# Auction_Single_RevB_Final.net
KiCad netlist of a schematic drawn in EAGLE
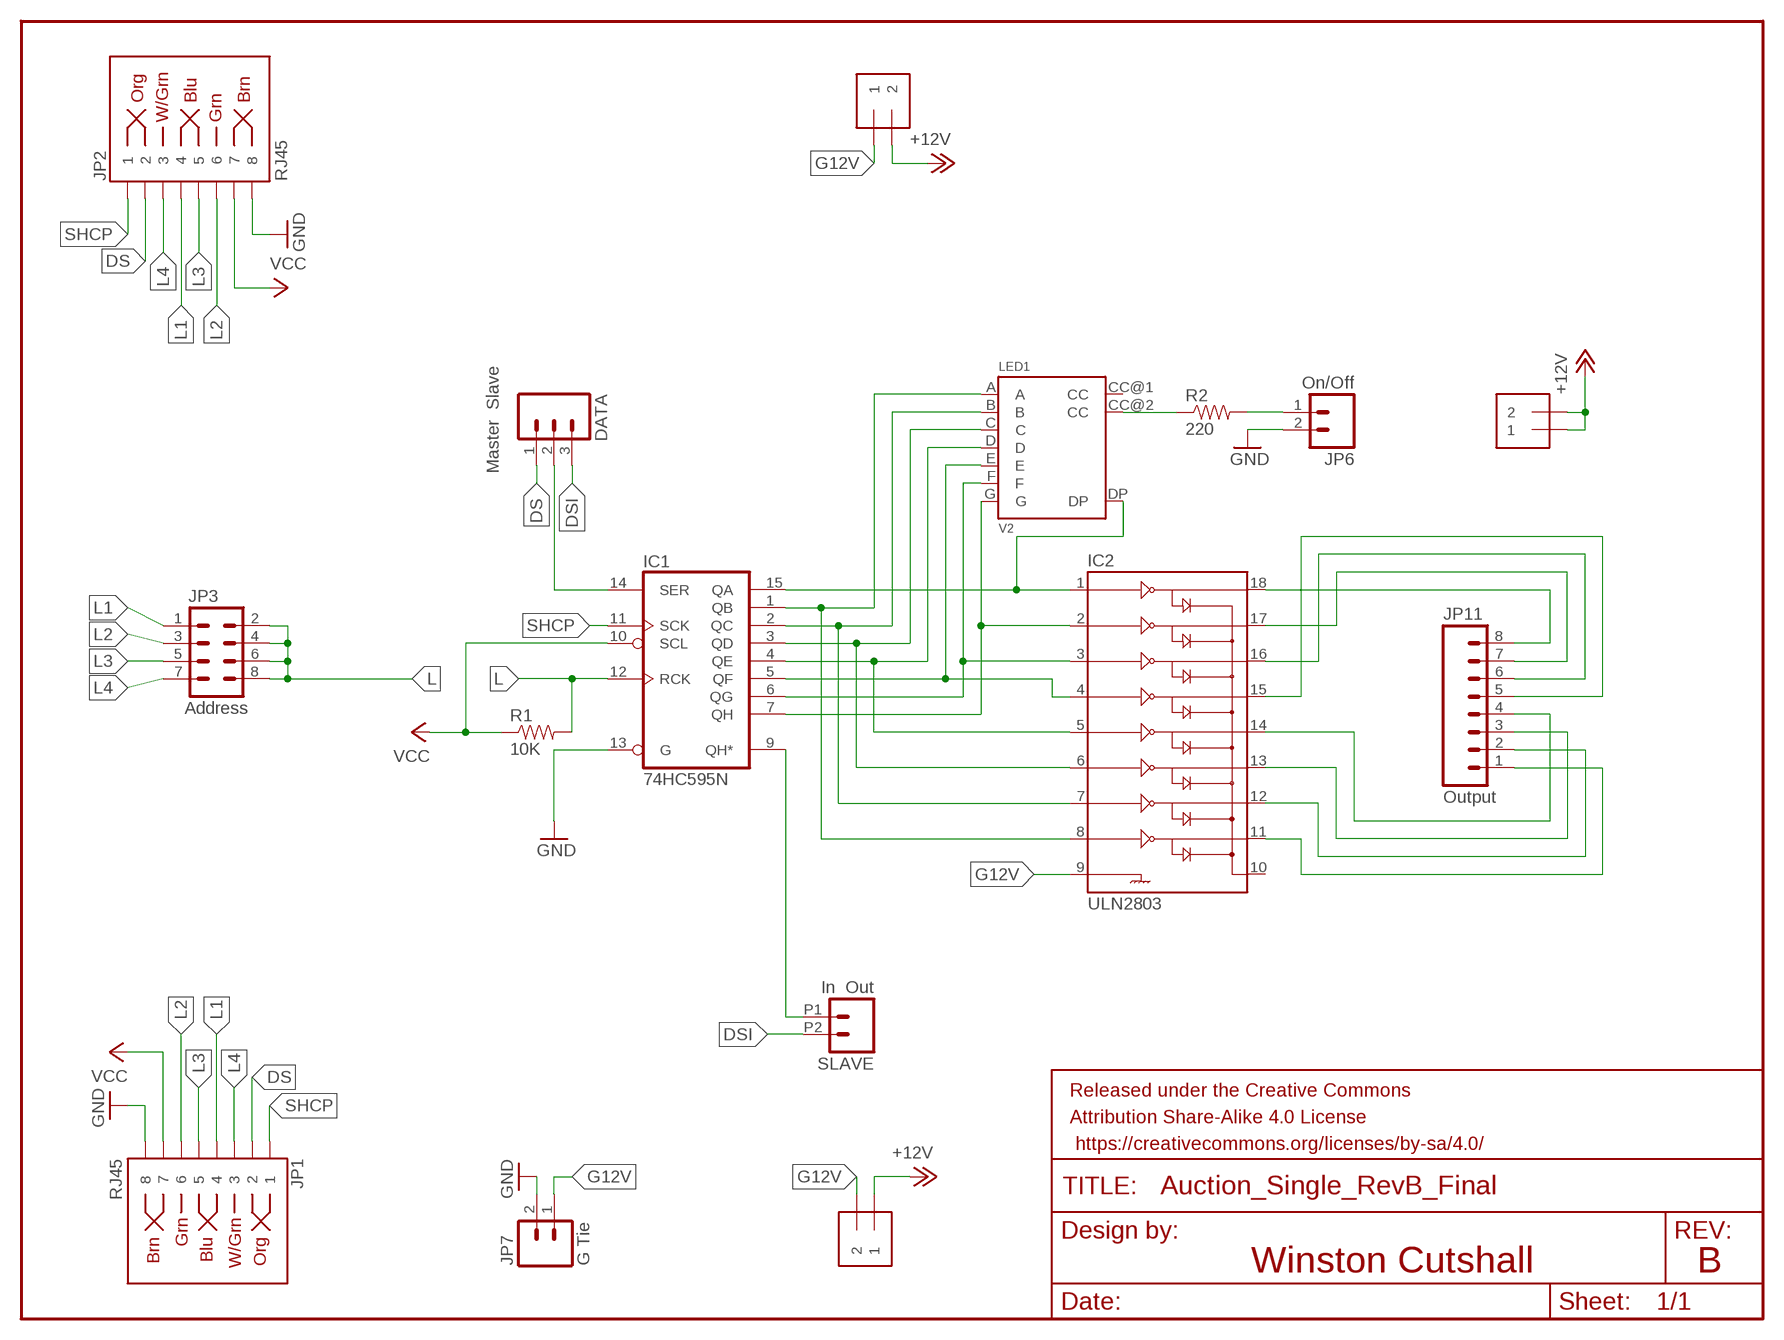
[diagram p0: schematic, sheet 1]

(export (version "E")
  (design (tool "Eeschema 10.0.6"))
  (components
    (comp (ref "DATA")
      (value "Master Slave")
      (footprint "eagle-import:1X03")
      (fields (field (name "MPN") "2211S-03G"))
      (libsource (lib "eagle-import") (part "M03PTH"))
    )
    (comp (ref "FRAME1")
      (value "FRAME-LETTER")
      (footprint "eagle-import:CREATIVE_COMMONS")
      (libsource (lib "eagle-import") (part "FRAME-LETTER"))
    )
    (comp (ref "IC1")
      (value "74HC595N")
      (footprint "eagle-import:DIL16")
      (fields (field (name "MF") "TEXAS INSTRUMENTS") (field (name "MPN") "SN74HC595N"))
      (libsource (lib "eagle-import") (part "74595NHC"))
    )
    (comp (ref "IC2")
      (value "ULN2803")
      (footprint "eagle-import:DIL18")
      (fields (field (name "MF") "Arrow Electronics") (field (name "MPN") "ULN2803A"))
      (libsource (lib "eagle-import") (part "ULN2803DIP"))
    )
    (comp (ref "JP1")
      (value "RJ45")
      (footprint "eagle-import:RJ45-8")
      (fields (field (name "MPN") "54602-908LF"))
      (libsource (lib "eagle-import") (part "RJ45-8PTH"))
    )
    (comp (ref "JP2")
      (value "RJ45")
      (footprint "eagle-import:RJ45-8")
      (fields (field (name "MPN") "54602-908LF"))
      (libsource (lib "eagle-import") (part "RJ45-8PTH"))
    )
    (comp (ref "JP3")
      (value "Address")
      (footprint "eagle-import:2X4")
      (fields (field (name "MPN") "M20-9980446"))
      (libsource (lib "eagle-import") (part "M04X2"))
    )
    (comp (ref "JP6")
      (value "On/Off")
      (footprint "eagle-import:1X02")
      (fields (field (name "MPN") "2211S-02G"))
      (libsource (lib "eagle-import") (part "M02PTH"))
    )
    (comp (ref "JP7")
      (value "G Tie")
      (footprint "eagle-import:1X02")
      (fields (field (name "MPN") "2211S-02G"))
      (libsource (lib "eagle-import") (part "M02PTH"))
    )
    (comp (ref "JP8")
      (value "1X2-3.5MM")
      (footprint "eagle-import:1X2-3.5MM")
      (fields (field (name "MPN") "1776275-2"))
      (libsource (lib "eagle-import") (part "1X2-3.5MM"))
    )
    (comp (ref "JP9")
      (value "1X2-3.5MM")
      (footprint "eagle-import:1X2-3.5MM")
      (fields (field (name "MPN") "1776275-2"))
      (libsource (lib "eagle-import") (part "1X2-3.5MM"))
    )
    (comp (ref "JP10")
      (value "1X2-3.5MM")
      (footprint "eagle-import:1X2-3.5MM")
      (fields (field (name "MPN") "1776275-2"))
      (libsource (lib "eagle-import") (part "1X2-3.5MM"))
    )
    (comp (ref "JP11")
      (value "Output")
      (footprint "eagle-import:SCREWTERMINAL-3.5MM-8")
      (fields (field (name "MPN") "20020327-C081B01LF"))
      (libsource (lib "eagle-import") (part "M083.5MM-8"))
    )
    (comp (ref "LED1")
      (value "V2")
      (footprint "eagle-import:HDSP-C3X3")
      (libsource (lib "eagle-import") (part "HDSP-C3X3"))
    )
    (comp (ref "R1")
      (value "10K")
      (footprint "eagle-import:AXIAL-0.3EZ")
      (fields (field (name "MF") "FARNELL") (field (name "MPN") "MCF 0.25W 10K"))
      (libsource (lib "eagle-import") (part "RESISTOREZ"))
    )
    (comp (ref "R2")
      (value "220")
      (footprint "eagle-import:AXIAL-0.3EZ")
      (fields (field (name "MF") "FARNELL") (field (name "MPN") "MCF 0.25W 220R"))
      (libsource (lib "eagle-import") (part "RESISTOREZ"))
    )
    (comp (ref "SLAVE")
      (value "In Out")
      (footprint "eagle-import:1X02_2.54_SCREWTERM")
      (fields (field (name "MF") "TYCO ELECTRONICS") (field (name "MPN") "282834-2"))
      (libsource (lib "eagle-import") (part "M022.54MM_SCREWTERM"))
    )
  )
  (nets
    (net (code "1") (name "+12V") (class "Default")
      (node (ref "JP10") (pin "1") (pinfunction "1_1") (pintype "passive"))
      (node (ref "JP10") (pin "2") (pinfunction "2_2") (pintype "passive"))
      (node (ref "JP8") (pin "1") (pinfunction "1_1") (pintype "passive"))
      (node (ref "JP9") (pin "2") (pinfunction "2_2") (pintype "passive"))
    )
    (net (code "2") (name "DS") (class "Default")
      (node (ref "DATA") (pin "1") (pinfunction "1_1") (pintype "passive"))
      (node (ref "JP1") (pin "2") (pinfunction "2_2") (pintype "bidirectional"))
      (node (ref "JP2") (pin "2") (pinfunction "2_2") (pintype "bidirectional"))
    )
    (net (code "3") (name "DSI") (class "Default")
      (node (ref "DATA") (pin "3") (pinfunction "3_3") (pintype "passive"))
      (node (ref "SLAVE") (pin "P2") (pinfunction "2_P2") (pintype "passive"))
    )
    (net (code "4") (name "G12V") (class "Default")
      (node (ref "IC2") (pin "9") (pinfunction "9_9") (pintype "bidirectional"))
      (node (ref "JP7") (pin "1") (pinfunction "1_1") (pintype "passive"))
      (node (ref "JP8") (pin "2") (pinfunction "2_2") (pintype "passive"))
      (node (ref "JP9") (pin "1") (pinfunction "1_1") (pintype "passive"))
    )
    (net (code "5") (name "GND") (class "Default")
      (node (ref "IC1") (pin "13") (pinfunction "G_13") (pintype "input"))
      (node (ref "JP1") (pin "8") (pinfunction "8_8") (pintype "bidirectional"))
      (node (ref "JP2") (pin "8") (pinfunction "8_8") (pintype "bidirectional"))
      (node (ref "JP6") (pin "2") (pinfunction "2_2") (pintype "passive"))
      (node (ref "JP7") (pin "2") (pinfunction "2_2") (pintype "passive"))
    )
    (net (code "6") (name "L") (class "Default")
      (node (ref "IC1") (pin "12") (pinfunction "RCK_12") (pintype "input"))
      (node (ref "JP3") (pin "2") (pinfunction "2_2") (pintype "passive"))
      (node (ref "JP3") (pin "4") (pinfunction "4_4") (pintype "passive"))
      (node (ref "JP3") (pin "6") (pinfunction "6_6") (pintype "passive"))
      (node (ref "JP3") (pin "8") (pinfunction "8_8") (pintype "passive"))
      (node (ref "R1") (pin "P$2") (pinfunction "2_P$2") (pintype "passive"))
    )
    (net (code "7") (name "L1") (class "Default")
      (node (ref "JP1") (pin "4") (pinfunction "4_4") (pintype "bidirectional"))
      (node (ref "JP2") (pin "4") (pinfunction "4_4") (pintype "bidirectional"))
      (node (ref "JP3") (pin "1") (pinfunction "1_1") (pintype "passive"))
    )
    (net (code "8") (name "L2") (class "Default")
      (node (ref "JP1") (pin "6") (pinfunction "6_6") (pintype "bidirectional"))
      (node (ref "JP2") (pin "6") (pinfunction "6_6") (pintype "bidirectional"))
      (node (ref "JP3") (pin "3") (pinfunction "3_3") (pintype "passive"))
    )
    (net (code "9") (name "L3") (class "Default")
      (node (ref "JP1") (pin "5") (pinfunction "5_5") (pintype "bidirectional"))
      (node (ref "JP2") (pin "5") (pinfunction "5_5") (pintype "bidirectional"))
      (node (ref "JP3") (pin "5") (pinfunction "5_5") (pintype "passive"))
    )
    (net (code "10") (name "L4") (class "Default")
      (node (ref "JP1") (pin "3") (pinfunction "3_3") (pintype "bidirectional"))
      (node (ref "JP2") (pin "3") (pinfunction "3_3") (pintype "bidirectional"))
      (node (ref "JP3") (pin "7") (pinfunction "7_7") (pintype "passive"))
    )
    (net (code "11") (name "Net-(IC1A-QA)") (class "Default")
      (node (ref "IC1") (pin "15") (pinfunction "QA_15") (pintype "tri_state"))
      (node (ref "IC2") (pin "1") (pinfunction "1_1") (pintype "bidirectional"))
      (node (ref "LED1") (pin "DP") (pinfunction "DP_DP") (pintype "bidirectional"))
    )
    (net (code "12") (name "Net-(IC1A-QB)") (class "Default")
      (node (ref "IC1") (pin "1") (pinfunction "QB_1") (pintype "tri_state"))
      (node (ref "IC2") (pin "8") (pinfunction "8_8") (pintype "bidirectional"))
      (node (ref "LED1") (pin "A") (pinfunction "A_A") (pintype "bidirectional"))
    )
    (net (code "13") (name "Net-(IC1A-QC)") (class "Default")
      (node (ref "IC1") (pin "2") (pinfunction "QC_2") (pintype "tri_state"))
      (node (ref "IC2") (pin "7") (pinfunction "7_7") (pintype "bidirectional"))
      (node (ref "LED1") (pin "B") (pinfunction "B_B") (pintype "bidirectional"))
    )
    (net (code "14") (name "Net-(IC1A-QD)") (class "Default")
      (node (ref "IC1") (pin "3") (pinfunction "QD_3") (pintype "tri_state"))
      (node (ref "IC2") (pin "6") (pinfunction "6_6") (pintype "bidirectional"))
      (node (ref "LED1") (pin "C") (pinfunction "C_C") (pintype "bidirectional"))
    )
    (net (code "15") (name "Net-(IC1A-QE)") (class "Default")
      (node (ref "IC1") (pin "4") (pinfunction "QE_4") (pintype "tri_state"))
      (node (ref "IC2") (pin "5") (pinfunction "5_5") (pintype "bidirectional"))
      (node (ref "LED1") (pin "D") (pinfunction "D_D") (pintype "bidirectional"))
    )
    (net (code "16") (name "Net-(IC1A-QF)") (class "Default")
      (node (ref "IC1") (pin "5") (pinfunction "QF_5") (pintype "tri_state"))
      (node (ref "IC2") (pin "4") (pinfunction "4_4") (pintype "bidirectional"))
      (node (ref "LED1") (pin "E") (pinfunction "E_E") (pintype "bidirectional"))
    )
    (net (code "17") (name "Net-(IC1A-QG)") (class "Default")
      (node (ref "IC1") (pin "6") (pinfunction "QG_6") (pintype "tri_state"))
      (node (ref "IC2") (pin "3") (pinfunction "3_3") (pintype "bidirectional"))
      (node (ref "LED1") (pin "F") (pinfunction "F_F") (pintype "bidirectional"))
    )
    (net (code "18") (name "Net-(IC1A-QH)") (class "Default")
      (node (ref "IC1") (pin "7") (pinfunction "QH_7") (pintype "tri_state"))
      (node (ref "IC2") (pin "2") (pinfunction "2_2") (pintype "bidirectional"))
      (node (ref "LED1") (pin "G") (pinfunction "G_G") (pintype "bidirectional"))
    )
    (net (code "19") (name "Net-(IC1A-QH*)") (class "Default")
      (node (ref "IC1") (pin "9") (pinfunction "QH*_9") (pintype "tri_state"))
      (node (ref "SLAVE") (pin "P1") (pinfunction "1_P1") (pintype "passive"))
    )
    (net (code "20") (name "Net-(IC1A-SER)") (class "Default")
      (node (ref "DATA") (pin "2") (pinfunction "2_2") (pintype "passive"))
      (node (ref "IC1") (pin "14") (pinfunction "SER_14") (pintype "input"))
    )
    (net (code "21") (name "Net-(IC2-Pad11)") (class "Default")
      (node (ref "IC2") (pin "11") (pinfunction "11_11") (pintype "bidirectional"))
      (node (ref "JP11") (pin "1") (pinfunction "1_1") (pintype "passive"))
    )
    (net (code "22") (name "Net-(IC2-Pad12)") (class "Default")
      (node (ref "IC2") (pin "12") (pinfunction "12_12") (pintype "bidirectional"))
      (node (ref "JP11") (pin "2") (pinfunction "2_2") (pintype "passive"))
    )
    (net (code "23") (name "Net-(IC2-Pad13)") (class "Default")
      (node (ref "IC2") (pin "13") (pinfunction "13_13") (pintype "bidirectional"))
      (node (ref "JP11") (pin "3") (pinfunction "3_3") (pintype "passive"))
    )
    (net (code "24") (name "Net-(IC2-Pad14)") (class "Default")
      (node (ref "IC2") (pin "14") (pinfunction "14_14") (pintype "bidirectional"))
      (node (ref "JP11") (pin "4") (pinfunction "4_4") (pintype "passive"))
    )
    (net (code "25") (name "Net-(IC2-Pad15)") (class "Default")
      (node (ref "IC2") (pin "15") (pinfunction "15_15") (pintype "bidirectional"))
      (node (ref "JP11") (pin "5") (pinfunction "5_5") (pintype "passive"))
    )
    (net (code "26") (name "Net-(IC2-Pad16)") (class "Default")
      (node (ref "IC2") (pin "16") (pinfunction "16_16") (pintype "bidirectional"))
      (node (ref "JP11") (pin "6") (pinfunction "6_6") (pintype "passive"))
    )
    (net (code "27") (name "Net-(IC2-Pad17)") (class "Default")
      (node (ref "IC2") (pin "17") (pinfunction "17_17") (pintype "bidirectional"))
      (node (ref "JP11") (pin "7") (pinfunction "7_7") (pintype "passive"))
    )
    (net (code "28") (name "Net-(IC2-Pad18)") (class "Default")
      (node (ref "IC2") (pin "18") (pinfunction "18_18") (pintype "bidirectional"))
      (node (ref "JP11") (pin "8") (pinfunction "8_8") (pintype "passive"))
    )
    (net (code "29") (name "Net-(R2-1)") (class "Default")
      (node (ref "LED1") (pin "CC@2") (pinfunction "CC_CC@2") (pintype "bidirectional"))
      (node (ref "R2") (pin "P$1") (pinfunction "1_P$1") (pintype "passive"))
    )
    (net (code "30") (name "Net-(R2-2)") (class "Default")
      (node (ref "JP6") (pin "1") (pinfunction "1_1") (pintype "passive"))
      (node (ref "R2") (pin "P$2") (pinfunction "2_P$2") (pintype "passive"))
    )
    (net (code "31") (name "SHCP") (class "Default")
      (node (ref "IC1") (pin "11") (pinfunction "SCK_11") (pintype "input"))
      (node (ref "JP1") (pin "1") (pinfunction "1_1") (pintype "bidirectional"))
      (node (ref "JP2") (pin "1") (pinfunction "1_1") (pintype "bidirectional"))
    )
    (net (code "32") (name "VCC") (class "Default")
      (node (ref "IC1") (pin "10") (pinfunction "SCL_10") (pintype "input"))
      (node (ref "JP1") (pin "7") (pinfunction "7_7") (pintype "bidirectional"))
      (node (ref "JP2") (pin "7") (pinfunction "7_7") (pintype "bidirectional"))
      (node (ref "R1") (pin "P$1") (pinfunction "1_P$1") (pintype "passive"))
    )
    (net (code "33") (name "unconnected-(IC2-Pad10)") (class "Default")
      (node (ref "IC2") (pin "10") (pinfunction "10_10") (pintype "bidirectional"))
    )
    (net (code "34") (name "unconnected-(LED1-CC-PadCC@1)") (class "Default")
      (node (ref "LED1") (pin "CC@1") (pinfunction "CC_CC@1") (pintype "bidirectional"))
    )
  )
)
